# RX1.net
KiCad netlist of a schematic drawn in Altium Designer
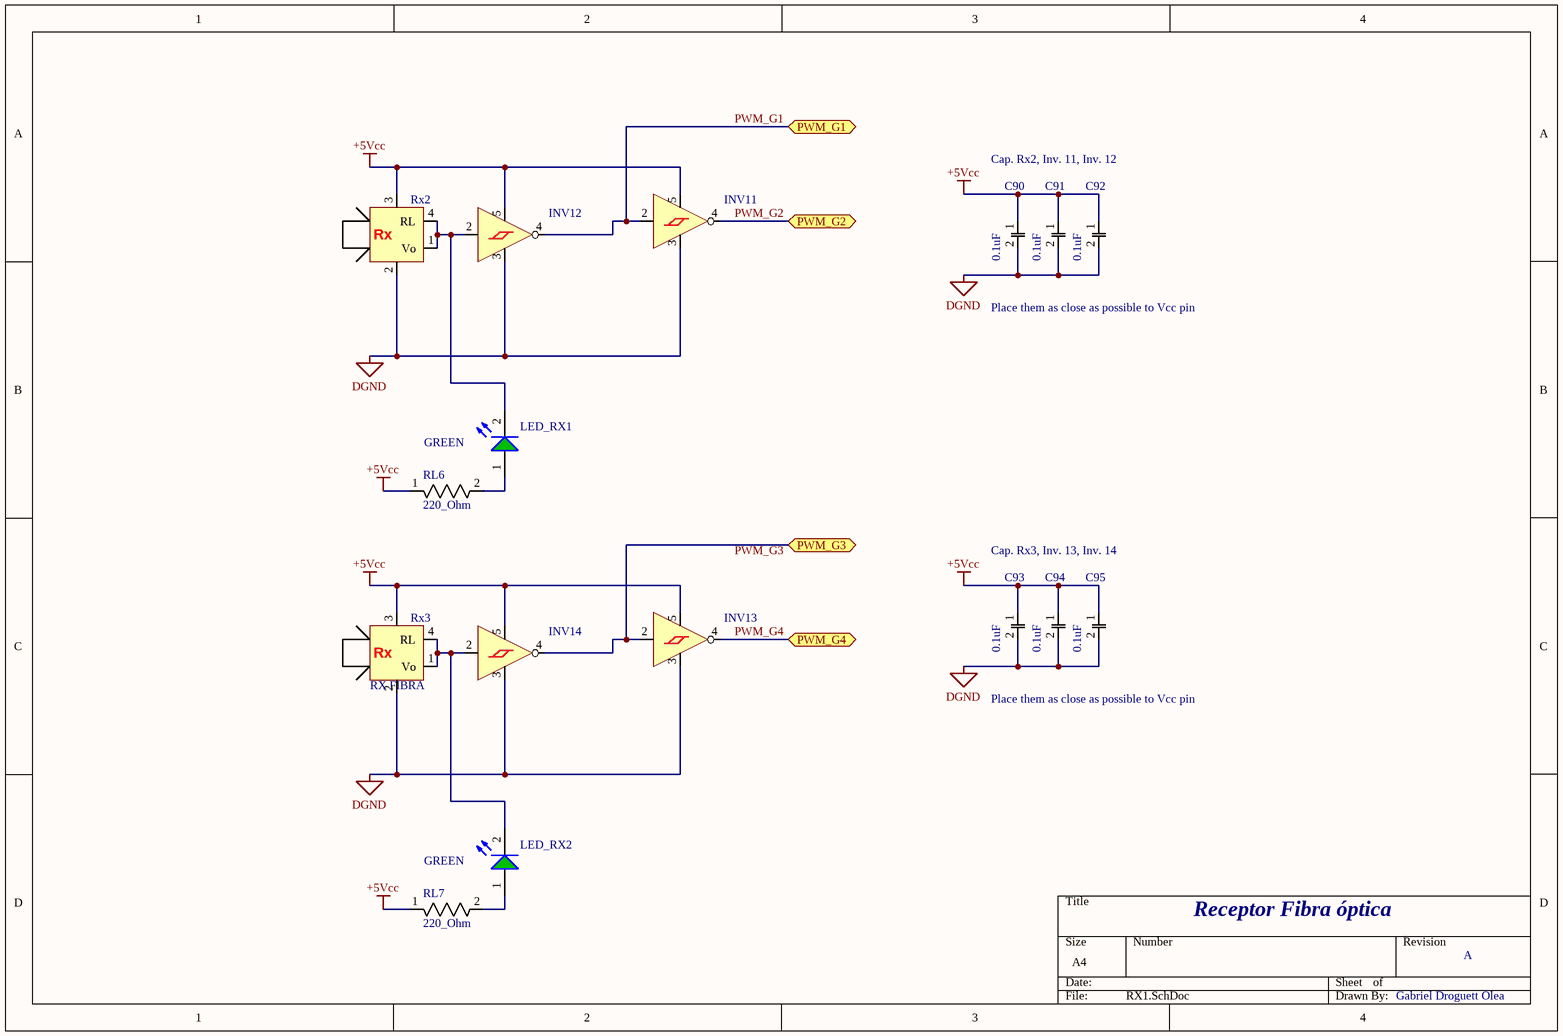
[diagram p0: RX1.SchDoc]

(export (version "E")
  (design (tool "Eeschema 10.0.6"))
  (components
    (comp (ref "C90")
      (value "0.1uF")
      (footprint "CAP_0603")
      (description "0.1µF ±10% 16V Ceramic Capacitor X7R 0603 (1608 Metric)")
      (fields
        (field (name "DIGI-KEY PART NUMBER") "478-1239-1-ND")
        (field (name "MANUFACTURER PART NUMBER") "0603YC104KAT2A")
      )
      (libsource (lib "CAP01uF_0603YC104KAT2A") (part "CAP_0603YC104KAT2A"))
    )
    (comp (ref "C91")
      (value "0.1uF")
      (footprint "CAP_0603")
      (description "0.1µF ±10% 16V Ceramic Capacitor X7R 0603 (1608 Metric)")
      (fields
        (field (name "DIGI-KEY PART NUMBER") "478-1239-1-ND")
        (field (name "MANUFACTURER PART NUMBER") "0603YC104KAT2A")
      )
      (libsource (lib "CAP01uF_0603YC104KAT2A") (part "CAP_0603YC104KAT2A"))
    )
    (comp (ref "C92")
      (value "0.1uF")
      (footprint "CAP_0603")
      (description "0.1µF ±10% 16V Ceramic Capacitor X7R 0603 (1608 Metric)")
      (fields
        (field (name "DIGI-KEY PART NUMBER") "478-1239-1-ND")
        (field (name "MANUFACTURER PART NUMBER") "0603YC104KAT2A")
      )
      (libsource (lib "CAP01uF_0603YC104KAT2A") (part "CAP_0603YC104KAT2A"))
    )
    (comp (ref "C93")
      (value "0.1uF")
      (footprint "CAP_0603")
      (description "0.1µF ±10% 16V Ceramic Capacitor X7R 0603 (1608 Metric)")
      (fields
        (field (name "DIGI-KEY PART NUMBER") "478-1239-1-ND")
        (field (name "MANUFACTURER PART NUMBER") "0603YC104KAT2A")
      )
      (libsource (lib "CAP01uF_0603YC104KAT2A") (part "CAP_0603YC104KAT2A"))
    )
    (comp (ref "C94")
      (value "0.1uF")
      (footprint "CAP_0603")
      (description "0.1µF ±10% 16V Ceramic Capacitor X7R 0603 (1608 Metric)")
      (fields
        (field (name "DIGI-KEY PART NUMBER") "478-1239-1-ND")
        (field (name "MANUFACTURER PART NUMBER") "0603YC104KAT2A")
      )
      (libsource (lib "CAP01uF_0603YC104KAT2A") (part "CAP_0603YC104KAT2A"))
    )
    (comp (ref "C95")
      (value "0.1uF")
      (footprint "CAP_0603")
      (description "0.1µF ±10% 16V Ceramic Capacitor X7R 0603 (1608 Metric)")
      (fields
        (field (name "DIGI-KEY PART NUMBER") "478-1239-1-ND")
        (field (name "MANUFACTURER PART NUMBER") "0603YC104KAT2A")
      )
      (libsource (lib "CAP01uF_0603YC104KAT2A") (part "CAP_0603YC104KAT2A"))
    )
    (comp (ref "INV11")
      (value "NOT SCHMITT")
      (footprint "INV_SN74AHC1G14DBVR")
      (description "IC SCHMITT-TRG INV GATE SOT23-5")
      (fields
        (field (name "DIGI-KEY PART NUMBER") "296-1092-1-ND")
        (field (name "MANUFACTURER PART NUMBER") "SN74AHC1G14DBVR")
      )
      (libsource (lib "INV_SN74AHC1G14DBVR") (part "INV_SN74AHC1G14DBVR"))
    )
    (comp (ref "INV12")
      (value "NOT SCHMITT")
      (footprint "INV_SN74AHC1G14DBVR")
      (description "IC SCHMITT-TRG INV GATE SOT23-5")
      (fields
        (field (name "DIGI-KEY PART NUMBER") "296-1092-1-ND")
        (field (name "MANUFACTURER PART NUMBER") "SN74AHC1G14DBVR")
      )
      (libsource (lib "INV_SN74AHC1G14DBVR") (part "INV_SN74AHC1G14DBVR"))
    )
    (comp (ref "INV13")
      (value "NOT SCHMITT")
      (footprint "INV_SN74AHC1G14DBVR")
      (description "IC SCHMITT-TRG INV GATE SOT23-5")
      (fields
        (field (name "DIGI-KEY PART NUMBER") "296-1092-1-ND")
        (field (name "MANUFACTURER PART NUMBER") "SN74AHC1G14DBVR")
      )
      (libsource (lib "INV_SN74AHC1G14DBVR") (part "INV_SN74AHC1G14DBVR"))
    )
    (comp (ref "INV14")
      (value "NOT SCHMITT")
      (footprint "INV_SN74AHC1G14DBVR")
      (description "IC SCHMITT-TRG INV GATE SOT23-5")
      (fields
        (field (name "DIGI-KEY PART NUMBER") "296-1092-1-ND")
        (field (name "MANUFACTURER PART NUMBER") "SN74AHC1G14DBVR")
      )
      (libsource (lib "INV_SN74AHC1G14DBVR") (part "INV_SN74AHC1G14DBVR"))
    )
    (comp (ref "LED_RX1")
      (value "GREEN")
      (footprint "LED_0805")
      (description "LED GREEN DIFFUSED 0805 SMD")
      (fields
        (field (name "DIGI-KEY PART NUMBER") "475-1410-1-ND")
        (field (name "MANUFACTURER PART NUMBER") "LG R971-KN-1")
      )
      (libsource (lib "WL-SMCW_rev15b") (part "WL-SMCW 0805  150080GS75000"))
    )
    (comp (ref "LED_RX2")
      (value "GREEN")
      (footprint "LED_0805")
      (description "LED GREEN DIFFUSED 0805 SMD")
      (fields
        (field (name "DIGI-KEY PART NUMBER") "475-1410-1-ND")
        (field (name "MANUFACTURER PART NUMBER") "LG R971-KN-1")
      )
      (libsource (lib "WL-SMCW_rev15b") (part "WL-SMCW 0805  150080GS75000"))
    )
    (comp (ref "RL6")
      (value "220_Ohm")
      (footprint "res_0805")
      (description "1% 1/4W 0805")
      (fields
        (field (name "DIGI-KEY PART NUMBER") "311-220HRCT-ND")
        (field (name "MANUFACTURER PART NUMBER") "RC0603FR-07220RL")
      )
      (libsource (lib "RES470_ERJ-3GEYJ471V") (part "RES_ERJ-3GEYJ471V"))
    )
    (comp (ref "RL7")
      (value "220_Ohm")
      (footprint "res_0805")
      (description "1% 1/4W 0805")
      (fields
        (field (name "DIGI-KEY PART NUMBER") "311-220HRCT-ND")
        (field (name "MANUFACTURER PART NUMBER") "RC0603FR-07220RL")
      )
      (libsource (lib "RES470_ERJ-3GEYJ471V") (part "RES_ERJ-3GEYJ471V"))
    )
    (comp (ref "Rx2")
      (value "RX FIBRA")
      (footprint "Rx_HFBR-2521Z")
      (description "RECEIVER FIBER OPTIC 600NM 5MBD")
      (fields
        (field (name "DIGI-KEY PART NUMBER") "516-2062-ND")
        (field (name "MANUFACTURER PART NUMBER") "HFBR-2521Z")
      )
      (libsource (lib "Rx_HFBR-2521Z") (part "Rx_HFBR-2521Z"))
    )
    (comp (ref "Rx3")
      (value "RX FIBRA")
      (footprint "Rx_HFBR-2521Z")
      (description "RECEIVER FIBER OPTIC 600NM 5MBD")
      (fields
        (field (name "DIGI-KEY PART NUMBER") "516-2062-ND")
        (field (name "MANUFACTURER PART NUMBER") "HFBR-2521Z")
      )
      (libsource (lib "Rx_HFBR-2521Z") (part "Rx_HFBR-2521Z"))
    )
  )
  (nets
    (net (code "1") (name "+5Vcc") (class "Default")
      (node (ref "C90") (pin "1") (pinfunction "1_1") (pintype "passive"))
      (node (ref "C91") (pin "1") (pinfunction "1_1") (pintype "passive"))
      (node (ref "C92") (pin "1") (pinfunction "1_1") (pintype "passive"))
      (node (ref "C93") (pin "1") (pinfunction "1_1") (pintype "passive"))
      (node (ref "C94") (pin "1") (pinfunction "1_1") (pintype "passive"))
      (node (ref "C95") (pin "1") (pinfunction "1_1") (pintype "passive"))
      (node (ref "INV11") (pin "5") (pinfunction "Vcc_5") (pintype "passive"))
      (node (ref "INV12") (pin "5") (pinfunction "Vcc_5") (pintype "passive"))
      (node (ref "INV13") (pin "5") (pinfunction "Vcc_5") (pintype "passive"))
      (node (ref "INV14") (pin "5") (pinfunction "Vcc_5") (pintype "passive"))
      (node (ref "RL6") (pin "1") (pinfunction "C_1") (pintype "passive"))
      (node (ref "RL7") (pin "1") (pinfunction "C_1") (pintype "passive"))
      (node (ref "Rx2") (pin "3") (pinfunction "Vcc_3") (pintype "passive"))
      (node (ref "Rx3") (pin "3") (pinfunction "Vcc_3") (pintype "passive"))
    )
    (net (code "2") (name "/PWM_G1") (class "Default")
      (node (ref "INV11") (pin "2") (pinfunction "A_2") (pintype "passive"))
      (node (ref "INV12") (pin "4") (pinfunction "Vcc_4") (pintype "passive"))
    )
    (net (code "3") (name "/PWM_G2") (class "Default")
      (node (ref "INV11") (pin "4") (pinfunction "Vcc_4") (pintype "passive"))
    )
    (net (code "4") (name "/PWM_G3") (class "Default")
      (node (ref "INV13") (pin "2") (pinfunction "A_2") (pintype "passive"))
      (node (ref "INV14") (pin "4") (pinfunction "Vcc_4") (pintype "passive"))
    )
    (net (code "5") (name "/PWM_G4") (class "Default")
      (node (ref "INV13") (pin "4") (pinfunction "Vcc_4") (pintype "passive"))
    )
    (net (code "6") (name "DGND") (class "Default")
      (node (ref "C90") (pin "2") (pinfunction "2_2") (pintype "passive"))
      (node (ref "C91") (pin "2") (pinfunction "2_2") (pintype "passive"))
      (node (ref "C92") (pin "2") (pinfunction "2_2") (pintype "passive"))
      (node (ref "C93") (pin "2") (pinfunction "2_2") (pintype "passive"))
      (node (ref "C94") (pin "2") (pinfunction "2_2") (pintype "passive"))
      (node (ref "C95") (pin "2") (pinfunction "2_2") (pintype "passive"))
      (node (ref "INV11") (pin "3") (pinfunction "GND_3") (pintype "passive"))
      (node (ref "INV12") (pin "3") (pinfunction "GND_3") (pintype "passive"))
      (node (ref "INV13") (pin "3") (pinfunction "GND_3") (pintype "passive"))
      (node (ref "INV14") (pin "3") (pinfunction "GND_3") (pintype "passive"))
      (node (ref "Rx2") (pin "2") (pinfunction "GND_2") (pintype "passive"))
      (node (ref "Rx3") (pin "2") (pinfunction "GND_2") (pintype "passive"))
    )
    (net (code "7") (name "Net-(INV12-A)") (class "Default")
      (node (ref "INV12") (pin "2") (pinfunction "A_2") (pintype "passive"))
      (node (ref "LED_RX1") (pin "2") (pinfunction "C_2") (pintype "passive"))
      (node (ref "Rx2") (pin "1") (pinfunction "Vo_1") (pintype "passive"))
      (node (ref "Rx2") (pin "4") (pinfunction "RL_4") (pintype "passive"))
    )
    (net (code "8") (name "Net-(INV14-A)") (class "Default")
      (node (ref "INV14") (pin "2") (pinfunction "A_2") (pintype "passive"))
      (node (ref "LED_RX2") (pin "2") (pinfunction "C_2") (pintype "passive"))
      (node (ref "Rx3") (pin "1") (pinfunction "Vo_1") (pintype "passive"))
      (node (ref "Rx3") (pin "4") (pinfunction "RL_4") (pintype "passive"))
    )
    (net (code "9") (name "Net-(LED_RX1-A)") (class "Default")
      (node (ref "LED_RX1") (pin "1") (pinfunction "A_1") (pintype "passive"))
      (node (ref "RL6") (pin "2") (pinfunction "A_2") (pintype "passive"))
    )
    (net (code "10") (name "Net-(LED_RX2-A)") (class "Default")
      (node (ref "LED_RX2") (pin "1") (pinfunction "A_1") (pintype "passive"))
      (node (ref "RL7") (pin "2") (pinfunction "A_2") (pintype "passive"))
    )
    (net (code "11") (name "unconnected-(INV11-NC-Pad1)") (class "Default")
      (node (ref "INV11") (pin "1") (pinfunction "NC_1") (pintype "passive"))
    )
    (net (code "12") (name "unconnected-(INV12-NC-Pad1)") (class "Default")
      (node (ref "INV12") (pin "1") (pinfunction "NC_1") (pintype "passive"))
    )
    (net (code "13") (name "unconnected-(INV13-NC-Pad1)") (class "Default")
      (node (ref "INV13") (pin "1") (pinfunction "NC_1") (pintype "passive"))
    )
    (net (code "14") (name "unconnected-(INV14-NC-Pad1)") (class "Default")
      (node (ref "INV14") (pin "1") (pinfunction "NC_1") (pintype "passive"))
    )
    (net (code "15") (name "unconnected-(Rx2-NC-Pad5)") (class "Default")
      (node (ref "Rx2") (pin "5") (pinfunction "NC_5") (pintype "passive"))
    )
    (net (code "16") (name "unconnected-(Rx2-NC-Pad8)") (class "Default")
      (node (ref "Rx2") (pin "8") (pinfunction "NC_8") (pintype "passive"))
    )
    (net (code "17") (name "unconnected-(Rx3-NC-Pad5)") (class "Default")
      (node (ref "Rx3") (pin "5") (pinfunction "NC_5") (pintype "passive"))
    )
    (net (code "18") (name "unconnected-(Rx3-NC-Pad8)") (class "Default")
      (node (ref "Rx3") (pin "8") (pinfunction "NC_8") (pintype "passive"))
    )
  )
)
